# Controller_PCB.net
KiCad netlist of a schematic drawn in EasyEDA Pro
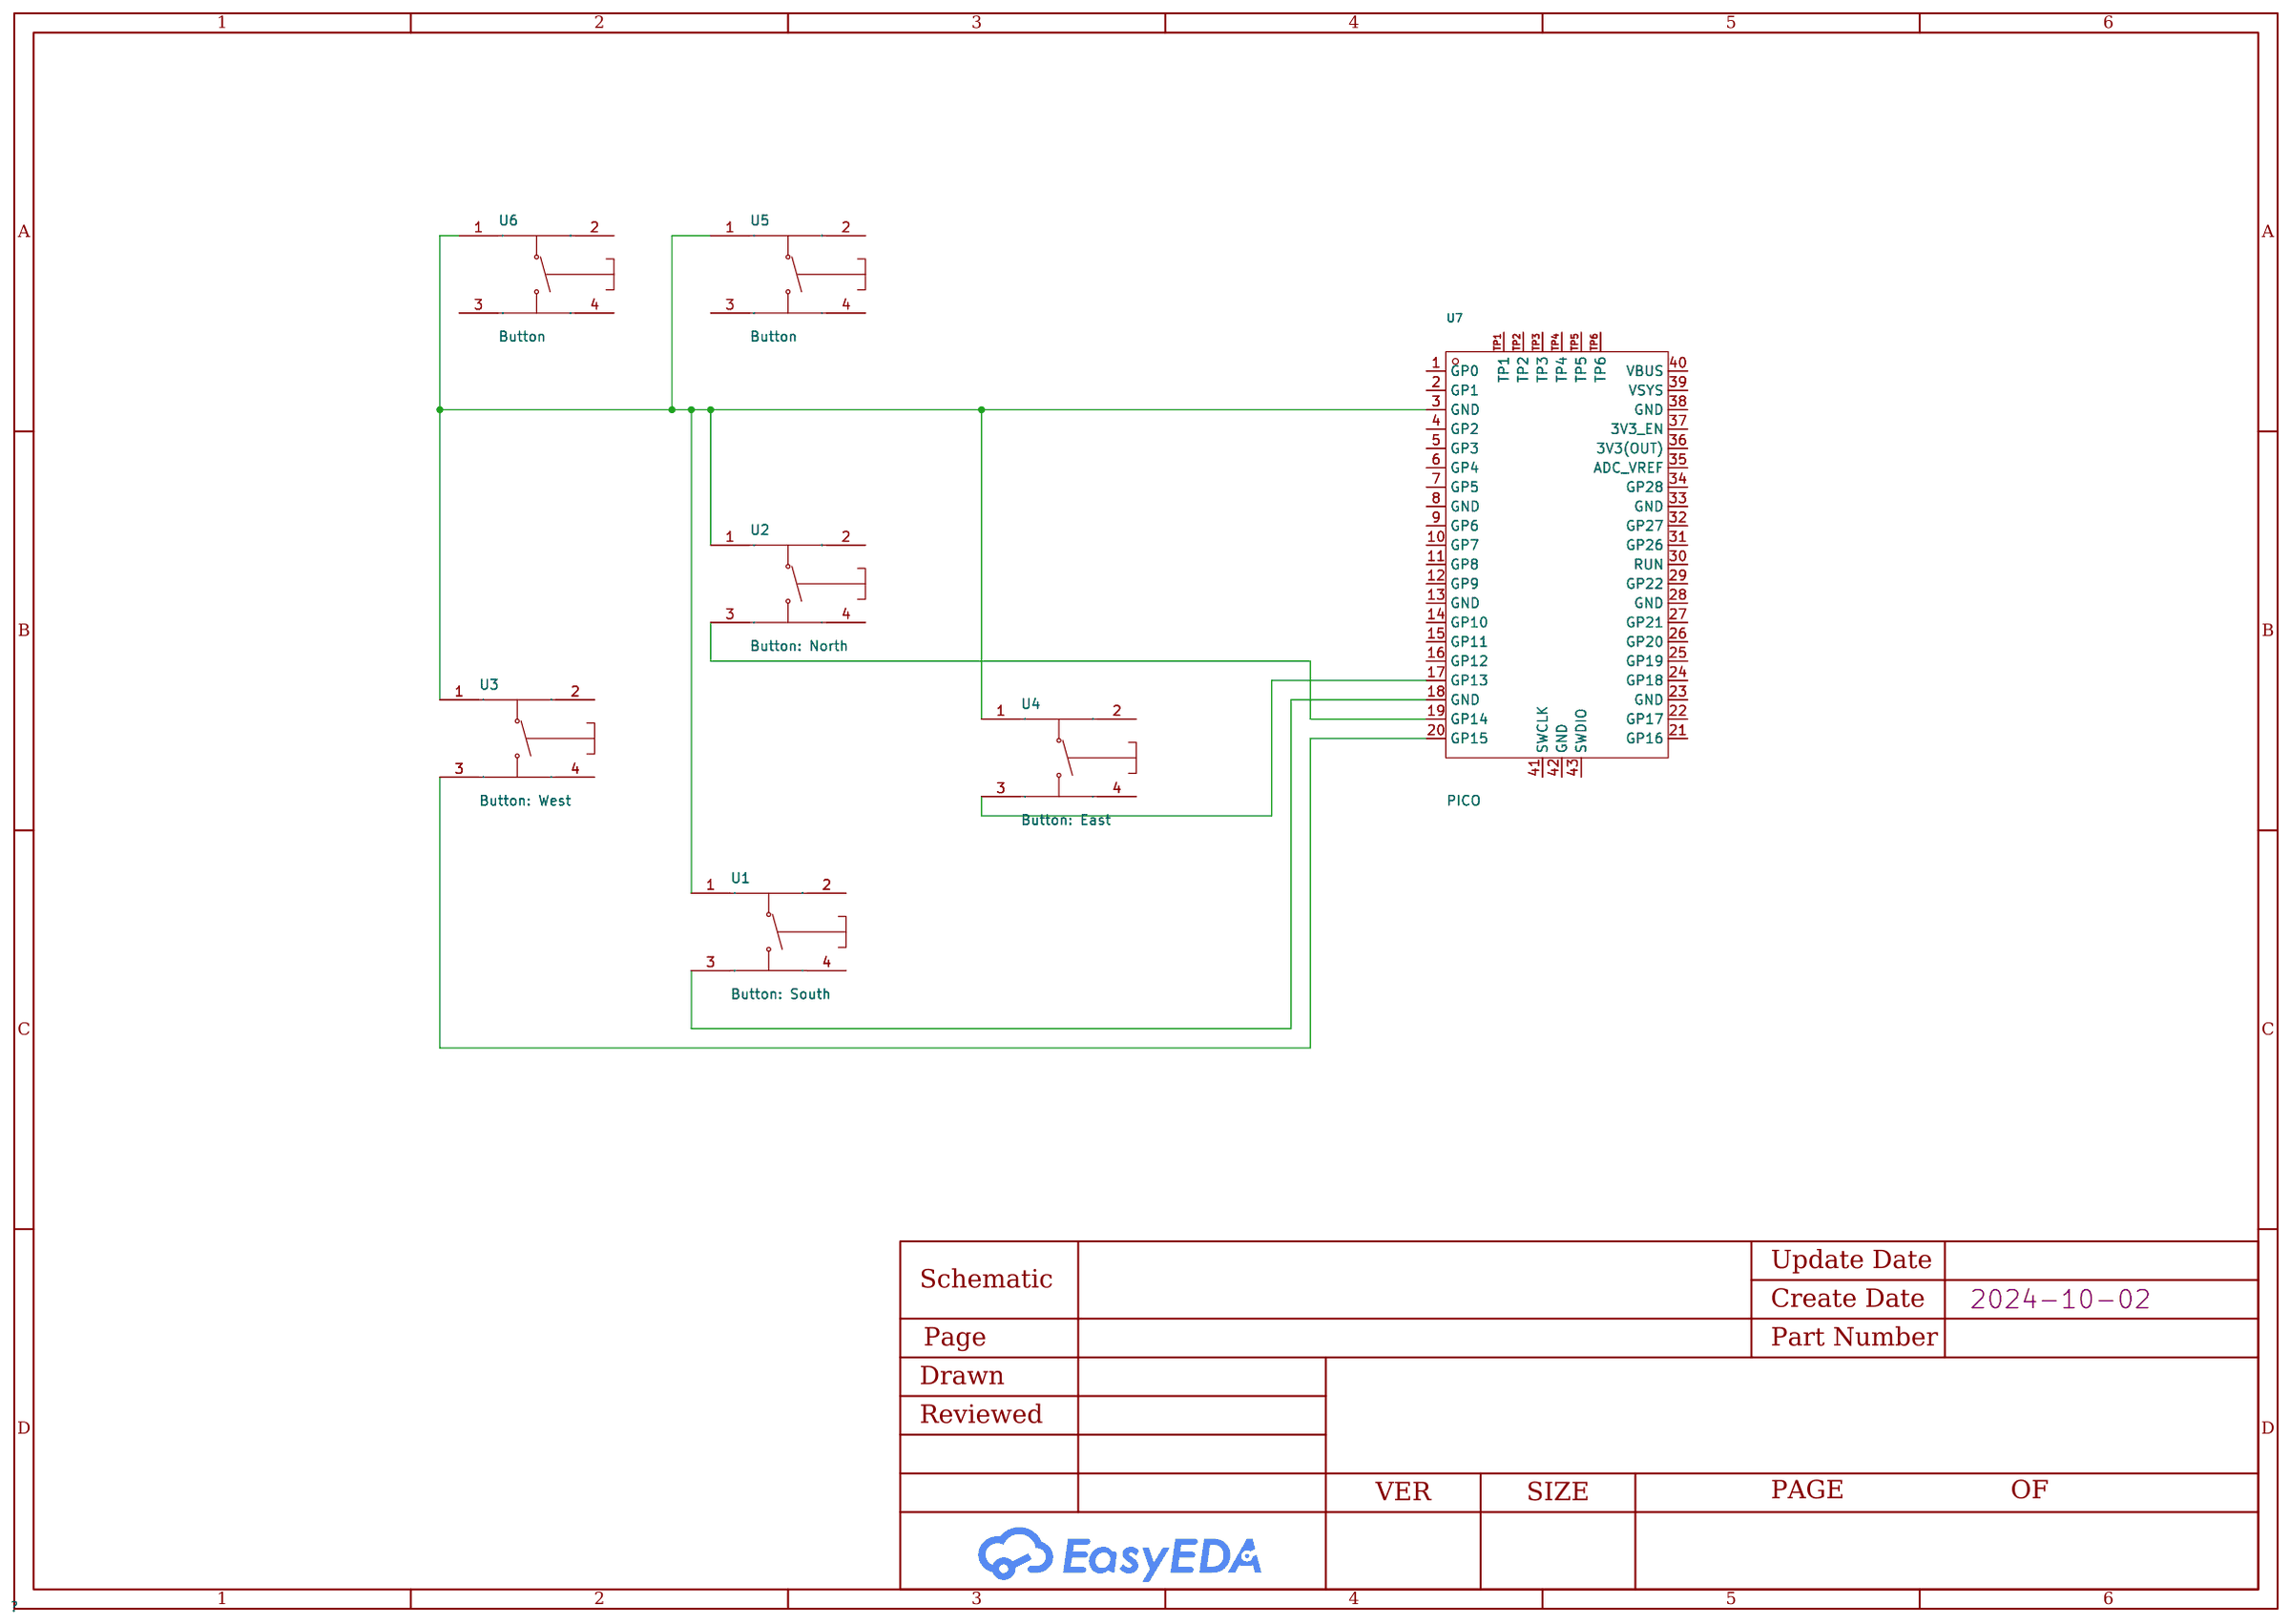
[diagram p0: schematic sheet]

(export (version "E")
  (design (tool "Eeschema 10.0.6"))
  (components
    (comp (ref "U1")
      (value "Button: South")
      (footprint "easyedapro:SW-SMD_4P-L5.1-W5.1-P3.70-LS6.5-TL-2")
      (fields (field (name "Manufacturer Part") "button"))
      (libsource (lib "easyedapro") (part "BUTTON_C9900016052"))
    )
    (comp (ref "U2")
      (value "Button: North")
      (footprint "easyedapro:SW-SMD_4P-L5.1-W5.1-P3.70-LS6.5-TL-2")
      (fields (field (name "Manufacturer Part") "button"))
      (libsource (lib "easyedapro") (part "BUTTON_C9900016052"))
    )
    (comp (ref "U3")
      (value "Button: West")
      (footprint "easyedapro:SW-SMD_4P-L5.1-W5.1-P3.70-LS6.5-TL-2")
      (fields (field (name "Manufacturer Part") "button"))
      (libsource (lib "easyedapro") (part "BUTTON_C9900016052"))
    )
    (comp (ref "U4")
      (value "Button: East")
      (footprint "easyedapro:SW-SMD_4P-L5.1-W5.1-P3.70-LS6.5-TL-2")
      (fields (field (name "Manufacturer Part") "button"))
      (libsource (lib "easyedapro") (part "BUTTON_C9900016052"))
    )
    (comp (ref "U5")
      (value "Button")
      (footprint "easyedapro:SW-SMD_4P-L5.1-W5.1-P3.70-LS6.5-TL-2")
      (fields (field (name "Manufacturer Part") "button"))
      (libsource (lib "easyedapro") (part "BUTTON_C9900016052"))
    )
    (comp (ref "U6")
      (value "Button")
      (footprint "easyedapro:SW-SMD_4P-L5.1-W5.1-P3.70-LS6.5-TL-2")
      (fields (field (name "Manufacturer Part") "button"))
      (libsource (lib "easyedapro") (part "BUTTON_C9900016052"))
    )
    (comp (ref "U7")
      (value "PICO")
      (footprint "easyedapro:COMM-SMD_L51.0-W21.0-P2.54_SC0916")
      (fields (field (name "Manufacturer") "Raspberry Pi(树莓派)"))
      (libsource (lib "easyedapro") (part "PICO"))
    )
  )
  (nets
    (net (code "1") (name "Net-(U1-Pad1)") (class "Default")
      (node (ref "U1") (pin "1") (pinfunction "1_1") (pintype "unspecified"))
      (node (ref "U2") (pin "1") (pinfunction "1_1") (pintype "unspecified"))
      (node (ref "U3") (pin "1") (pinfunction "1_1") (pintype "unspecified"))
      (node (ref "U4") (pin "1") (pinfunction "1_1") (pintype "unspecified"))
      (node (ref "U5") (pin "1") (pinfunction "1_1") (pintype "unspecified"))
      (node (ref "U6") (pin "1") (pinfunction "1_1") (pintype "unspecified"))
      (node (ref "U7") (pin "3") (pinfunction "GND_3") (pintype "input"))
    )
    (net (code "2") (name "Net-(U1-Pad3)") (class "Default")
      (node (ref "U1") (pin "3") (pinfunction "3_3") (pintype "unspecified"))
      (node (ref "U7") (pin "18") (pinfunction "GND_18") (pintype "input"))
    )
    (net (code "3") (name "Net-(U7-GP13)") (class "Default")
      (node (ref "U4") (pin "3") (pinfunction "3_3") (pintype "unspecified"))
      (node (ref "U7") (pin "17") (pinfunction "GP13_17") (pintype "input"))
    )
    (net (code "4") (name "Net-(U7-GP14)") (class "Default")
      (node (ref "U2") (pin "3") (pinfunction "3_3") (pintype "unspecified"))
      (node (ref "U7") (pin "19") (pinfunction "GP14_19") (pintype "input"))
    )
    (net (code "5") (name "Net-(U7-GP15)") (class "Default")
      (node (ref "U3") (pin "3") (pinfunction "3_3") (pintype "unspecified"))
      (node (ref "U7") (pin "20") (pinfunction "GP15_20") (pintype "input"))
    )
    (net (code "6") (name "unconnected-(U1-Pad2)") (class "Default")
      (node (ref "U1") (pin "2") (pinfunction "2_2") (pintype "unspecified"))
    )
    (net (code "7") (name "unconnected-(U1-Pad4)") (class "Default")
      (node (ref "U1") (pin "4") (pinfunction "4_4") (pintype "unspecified"))
    )
    (net (code "8") (name "unconnected-(U2-Pad2)") (class "Default")
      (node (ref "U2") (pin "2") (pinfunction "2_2") (pintype "unspecified"))
    )
    (net (code "9") (name "unconnected-(U2-Pad4)") (class "Default")
      (node (ref "U2") (pin "4") (pinfunction "4_4") (pintype "unspecified"))
    )
    (net (code "10") (name "unconnected-(U3-Pad2)") (class "Default")
      (node (ref "U3") (pin "2") (pinfunction "2_2") (pintype "unspecified"))
    )
    (net (code "11") (name "unconnected-(U3-Pad4)") (class "Default")
      (node (ref "U3") (pin "4") (pinfunction "4_4") (pintype "unspecified"))
    )
    (net (code "12") (name "unconnected-(U4-Pad2)") (class "Default")
      (node (ref "U4") (pin "2") (pinfunction "2_2") (pintype "unspecified"))
    )
    (net (code "13") (name "unconnected-(U4-Pad4)") (class "Default")
      (node (ref "U4") (pin "4") (pinfunction "4_4") (pintype "unspecified"))
    )
    (net (code "14") (name "unconnected-(U5-Pad2)") (class "Default")
      (node (ref "U5") (pin "2") (pinfunction "2_2") (pintype "unspecified"))
    )
    (net (code "15") (name "unconnected-(U5-Pad3)") (class "Default")
      (node (ref "U5") (pin "3") (pinfunction "3_3") (pintype "unspecified"))
    )
    (net (code "16") (name "unconnected-(U5-Pad4)") (class "Default")
      (node (ref "U5") (pin "4") (pinfunction "4_4") (pintype "unspecified"))
    )
    (net (code "17") (name "unconnected-(U6-Pad2)") (class "Default")
      (node (ref "U6") (pin "2") (pinfunction "2_2") (pintype "unspecified"))
    )
    (net (code "18") (name "unconnected-(U6-Pad3)") (class "Default")
      (node (ref "U6") (pin "3") (pinfunction "3_3") (pintype "unspecified"))
    )
    (net (code "19") (name "unconnected-(U6-Pad4)") (class "Default")
      (node (ref "U6") (pin "4") (pinfunction "4_4") (pintype "unspecified"))
    )
    (net (code "20") (name "unconnected-(U7-3V3(OUT)-Pad36)") (class "Default")
      (node (ref "U7") (pin "36") (pinfunction "3V3(OUT)_36") (pintype "input"))
    )
    (net (code "21") (name "unconnected-(U7-3V3_EN-Pad37)") (class "Default")
      (node (ref "U7") (pin "37") (pinfunction "3V3_EN_37") (pintype "input"))
    )
    (net (code "22") (name "unconnected-(U7-ADC_VREF-Pad35)") (class "Default")
      (node (ref "U7") (pin "35") (pinfunction "ADC_VREF_35") (pintype "input"))
    )
    (net (code "23") (name "unconnected-(U7-GND-Pad8)") (class "Default")
      (node (ref "U7") (pin "8") (pinfunction "GND_8") (pintype "input"))
    )
    (net (code "24") (name "unconnected-(U7-GND-Pad13)") (class "Default")
      (node (ref "U7") (pin "13") (pinfunction "GND_13") (pintype "input"))
    )
    (net (code "25") (name "unconnected-(U7-GND-Pad23)") (class "Default")
      (node (ref "U7") (pin "23") (pinfunction "GND_23") (pintype "input"))
    )
    (net (code "26") (name "unconnected-(U7-GND-Pad28)") (class "Default")
      (node (ref "U7") (pin "28") (pinfunction "GND_28") (pintype "input"))
    )
    (net (code "27") (name "unconnected-(U7-GND-Pad33)") (class "Default")
      (node (ref "U7") (pin "33") (pinfunction "GND_33") (pintype "input"))
    )
    (net (code "28") (name "unconnected-(U7-GND-Pad38)") (class "Default")
      (node (ref "U7") (pin "38") (pinfunction "GND_38") (pintype "input"))
    )
    (net (code "29") (name "unconnected-(U7-GND-Pad42)") (class "Default")
      (node (ref "U7") (pin "42") (pinfunction "GND_42") (pintype "input"))
    )
    (net (code "30") (name "unconnected-(U7-GP0-Pad1)") (class "Default")
      (node (ref "U7") (pin "1") (pinfunction "GP0_1") (pintype "input"))
    )
    (net (code "31") (name "unconnected-(U7-GP1-Pad2)") (class "Default")
      (node (ref "U7") (pin "2") (pinfunction "GP1_2") (pintype "input"))
    )
    (net (code "32") (name "unconnected-(U7-GP2-Pad4)") (class "Default")
      (node (ref "U7") (pin "4") (pinfunction "GP2_4") (pintype "input"))
    )
    (net (code "33") (name "unconnected-(U7-GP3-Pad5)") (class "Default")
      (node (ref "U7") (pin "5") (pinfunction "GP3_5") (pintype "input"))
    )
    (net (code "34") (name "unconnected-(U7-GP4-Pad6)") (class "Default")
      (node (ref "U7") (pin "6") (pinfunction "GP4_6") (pintype "input"))
    )
    (net (code "35") (name "unconnected-(U7-GP5-Pad7)") (class "Default")
      (node (ref "U7") (pin "7") (pinfunction "GP5_7") (pintype "input"))
    )
    (net (code "36") (name "unconnected-(U7-GP6-Pad9)") (class "Default")
      (node (ref "U7") (pin "9") (pinfunction "GP6_9") (pintype "input"))
    )
    (net (code "37") (name "unconnected-(U7-GP7-Pad10)") (class "Default")
      (node (ref "U7") (pin "10") (pinfunction "GP7_10") (pintype "input"))
    )
    (net (code "38") (name "unconnected-(U7-GP8-Pad11)") (class "Default")
      (node (ref "U7") (pin "11") (pinfunction "GP8_11") (pintype "input"))
    )
    (net (code "39") (name "unconnected-(U7-GP9-Pad12)") (class "Default")
      (node (ref "U7") (pin "12") (pinfunction "GP9_12") (pintype "input"))
    )
    (net (code "40") (name "unconnected-(U7-GP10-Pad14)") (class "Default")
      (node (ref "U7") (pin "14") (pinfunction "GP10_14") (pintype "input"))
    )
    (net (code "41") (name "unconnected-(U7-GP11-Pad15)") (class "Default")
      (node (ref "U7") (pin "15") (pinfunction "GP11_15") (pintype "input"))
    )
    (net (code "42") (name "unconnected-(U7-GP12-Pad16)") (class "Default")
      (node (ref "U7") (pin "16") (pinfunction "GP12_16") (pintype "input"))
    )
    (net (code "43") (name "unconnected-(U7-GP16-Pad21)") (class "Default")
      (node (ref "U7") (pin "21") (pinfunction "GP16_21") (pintype "input"))
    )
    (net (code "44") (name "unconnected-(U7-GP17-Pad22)") (class "Default")
      (node (ref "U7") (pin "22") (pinfunction "GP17_22") (pintype "input"))
    )
    (net (code "45") (name "unconnected-(U7-GP18-Pad24)") (class "Default")
      (node (ref "U7") (pin "24") (pinfunction "GP18_24") (pintype "input"))
    )
    (net (code "46") (name "unconnected-(U7-GP19-Pad25)") (class "Default")
      (node (ref "U7") (pin "25") (pinfunction "GP19_25") (pintype "input"))
    )
    (net (code "47") (name "unconnected-(U7-GP20-Pad26)") (class "Default")
      (node (ref "U7") (pin "26") (pinfunction "GP20_26") (pintype "input"))
    )
    (net (code "48") (name "unconnected-(U7-GP21-Pad27)") (class "Default")
      (node (ref "U7") (pin "27") (pinfunction "GP21_27") (pintype "input"))
    )
    (net (code "49") (name "unconnected-(U7-GP22-Pad29)") (class "Default")
      (node (ref "U7") (pin "29") (pinfunction "GP22_29") (pintype "input"))
    )
    (net (code "50") (name "unconnected-(U7-GP26-Pad31)") (class "Default")
      (node (ref "U7") (pin "31") (pinfunction "GP26_31") (pintype "input"))
    )
    (net (code "51") (name "unconnected-(U7-GP27-Pad32)") (class "Default")
      (node (ref "U7") (pin "32") (pinfunction "GP27_32") (pintype "input"))
    )
    (net (code "52") (name "unconnected-(U7-GP28-Pad34)") (class "Default")
      (node (ref "U7") (pin "34") (pinfunction "GP28_34") (pintype "input"))
    )
    (net (code "53") (name "unconnected-(U7-PadTP1)") (class "Default")
      (node (ref "U7") (pin "TP1") (pinfunction "TP1_TP1") (pintype "input"))
    )
    (net (code "54") (name "unconnected-(U7-PadTP2)") (class "Default")
      (node (ref "U7") (pin "TP2") (pinfunction "TP2_TP2") (pintype "input"))
    )
    (net (code "55") (name "unconnected-(U7-PadTP3)") (class "Default")
      (node (ref "U7") (pin "TP3") (pinfunction "TP3_TP3") (pintype "input"))
    )
    (net (code "56") (name "unconnected-(U7-PadTP4)") (class "Default")
      (node (ref "U7") (pin "TP4") (pinfunction "TP4_TP4") (pintype "input"))
    )
    (net (code "57") (name "unconnected-(U7-PadTP5)") (class "Default")
      (node (ref "U7") (pin "TP5") (pinfunction "TP5_TP5") (pintype "input"))
    )
    (net (code "58") (name "unconnected-(U7-PadTP6)") (class "Default")
      (node (ref "U7") (pin "TP6") (pinfunction "TP6_TP6") (pintype "input"))
    )
    (net (code "59") (name "unconnected-(U7-RUN-Pad30)") (class "Default")
      (node (ref "U7") (pin "30") (pinfunction "RUN_30") (pintype "input"))
    )
    (net (code "60") (name "unconnected-(U7-SWCLK-Pad41)") (class "Default")
      (node (ref "U7") (pin "41") (pinfunction "SWCLK_41") (pintype "input"))
    )
    (net (code "61") (name "unconnected-(U7-SWDIO-Pad43)") (class "Default")
      (node (ref "U7") (pin "43") (pinfunction "SWDIO_43") (pintype "input"))
    )
    (net (code "62") (name "unconnected-(U7-VBUS-Pad40)") (class "Default")
      (node (ref "U7") (pin "40") (pinfunction "VBUS_40") (pintype "input"))
    )
    (net (code "63") (name "unconnected-(U7-VSYS-Pad39)") (class "Default")
      (node (ref "U7") (pin "39") (pinfunction "VSYS_39") (pintype "input"))
    )
  )
)
